# ADX_IDCtoPinheader_adapter_2026-04-28.net
KiCad netlist of a schematic drawn in EasyEDA Pro
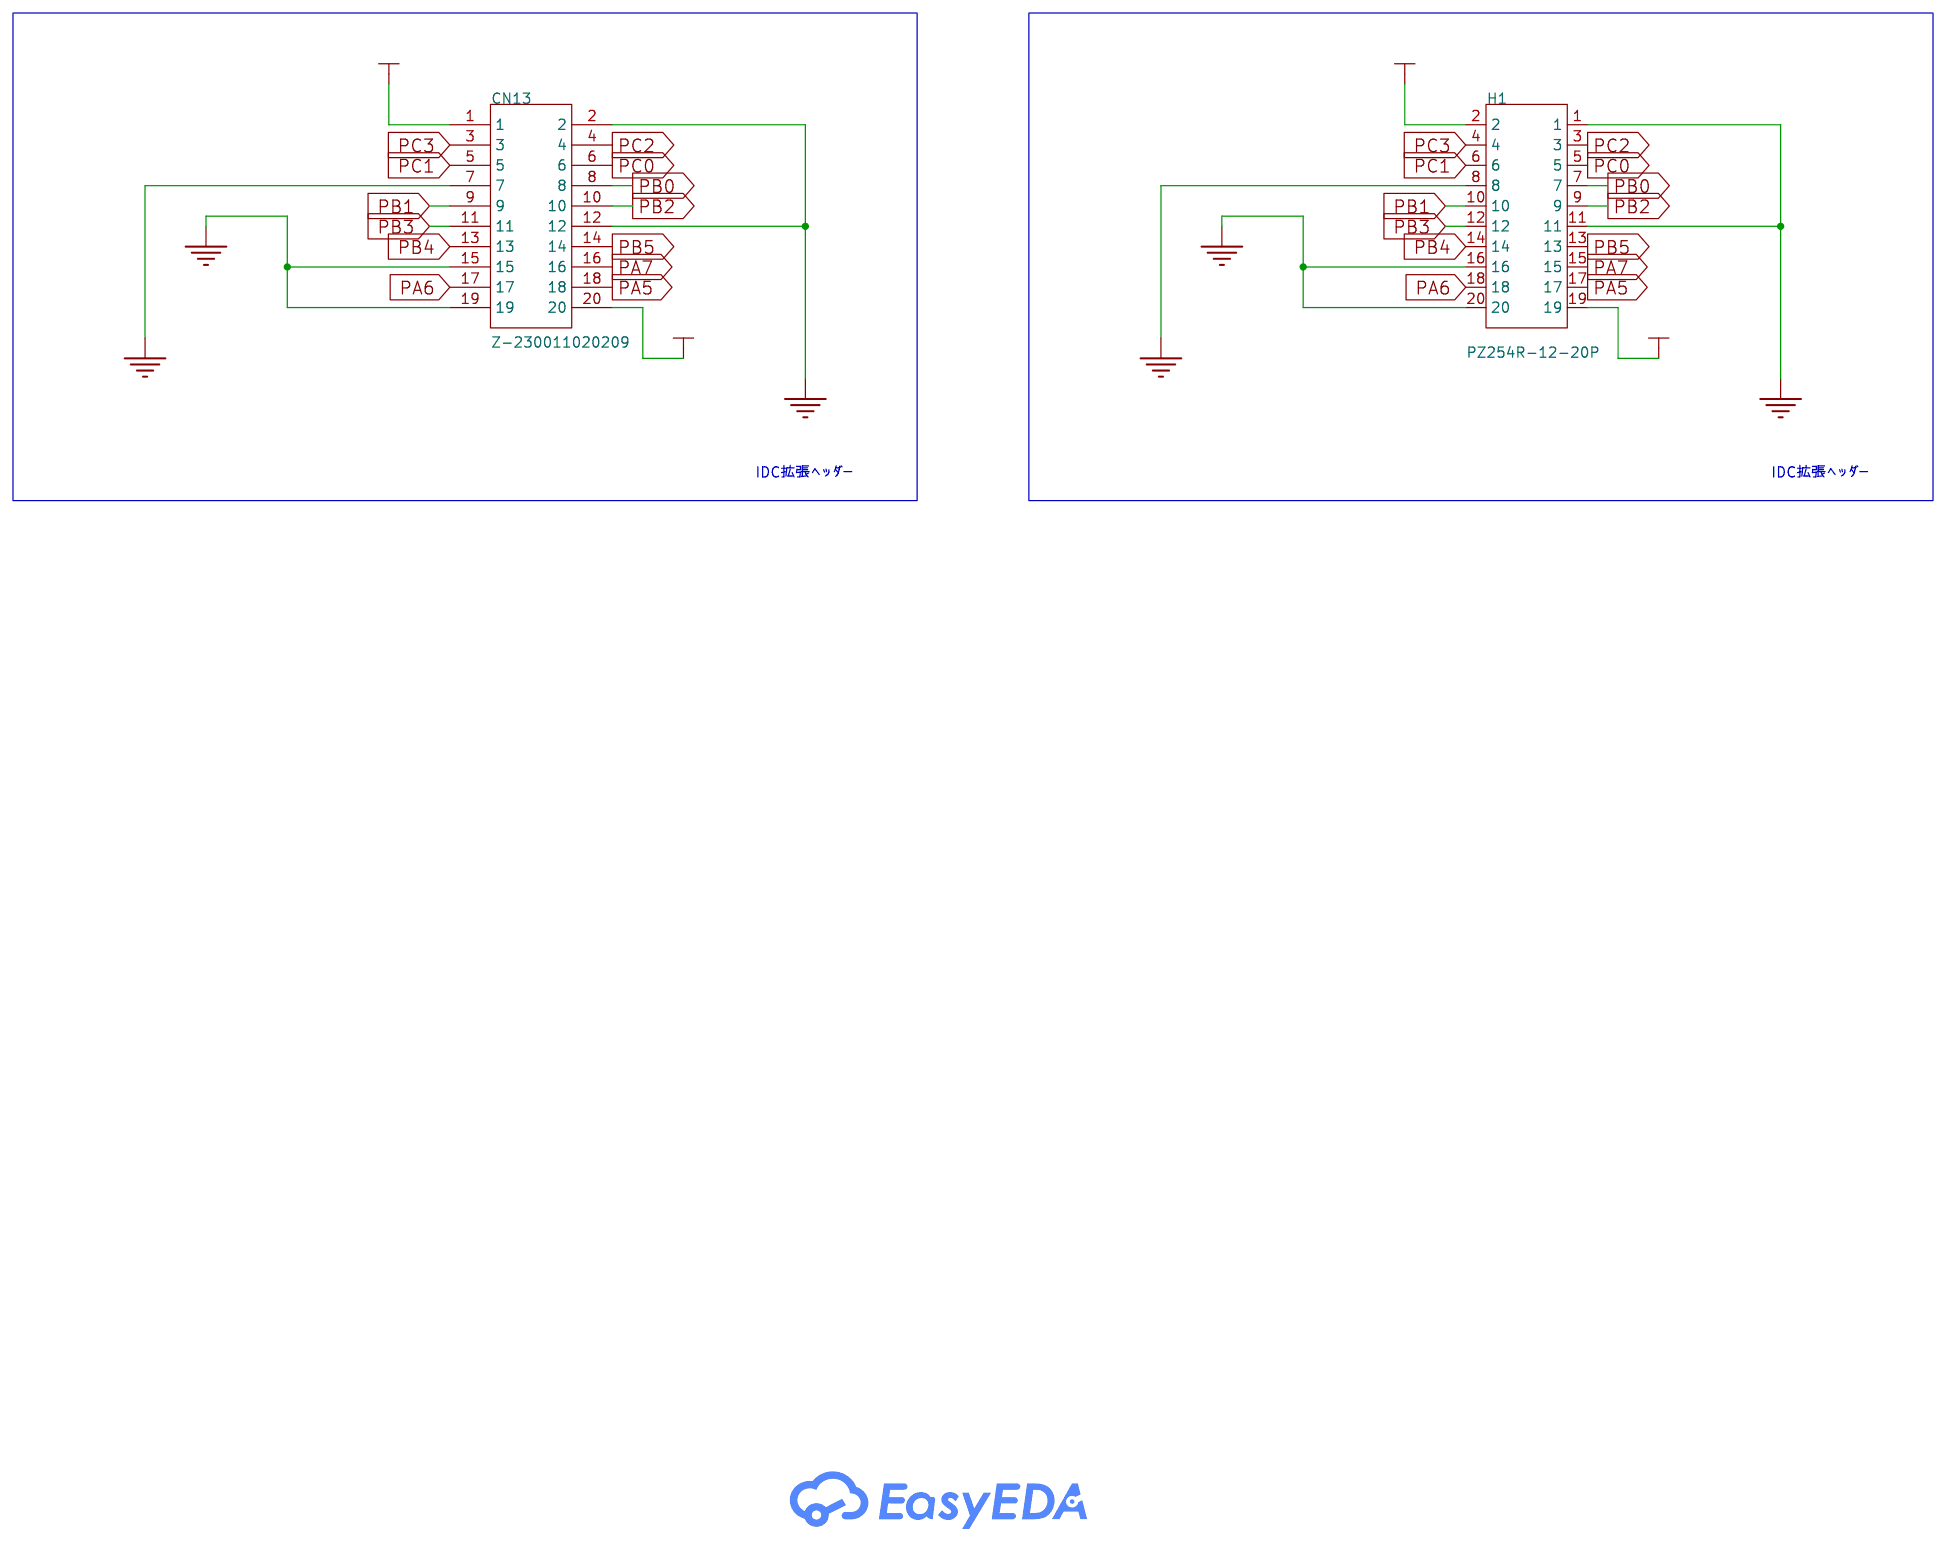
[diagram p0: schematic sheet]

(export (version "E")
  (design (tool "Eeschema 10.0.6"))
  (components
    (comp (ref "CN13")
      (value "Z-230011020209")
      (footprint "easyedapro:IDC-TH_20P-P2.54_Z-230011020209")
      (fields (field (name "Manufacturer") "Nextron(正凌)"))
      (libsource (lib "easyedapro") (part "Z-230011020209"))
    )
    (comp (ref "H1")
      (value "PZ254R-12-20P")
      (footprint "easyedapro:HDR-TH_20P-P2.54-H-M-R2-C10-S2.54")
      (fields (field (name "Manufacturer") "XFCN(兴飞)"))
      (libsource (lib "easyedapro") (part "PZ254R-12-20P"))
    )
  )
  (nets
    (net (code "1") (name "GND_5V") (class "Default")
      (node (ref "CN13") (pin "12") (pinfunction "12_12") (pintype "input"))
      (node (ref "CN13") (pin "15") (pinfunction "15_15") (pintype "input"))
      (node (ref "CN13") (pin "19") (pinfunction "19_19") (pintype "input"))
      (node (ref "CN13") (pin "2") (pinfunction "2_2") (pintype "input"))
      (node (ref "CN13") (pin "7") (pinfunction "7_7") (pintype "input"))
      (node (ref "H1") (pin "1") (pinfunction "1_1") (pintype "unspecified"))
      (node (ref "H1") (pin "11") (pinfunction "11_11") (pintype "unspecified"))
      (node (ref "H1") (pin "16") (pinfunction "16_16") (pintype "unspecified"))
      (node (ref "H1") (pin "20") (pinfunction "20_20") (pintype "unspecified"))
      (node (ref "H1") (pin "8") (pinfunction "8_8") (pintype "unspecified"))
    )
    (net (code "2") (name "PA5") (class "Default")
      (node (ref "CN13") (pin "18") (pinfunction "18_18") (pintype "input"))
      (node (ref "H1") (pin "17") (pinfunction "17_17") (pintype "unspecified"))
    )
    (net (code "3") (name "PA6") (class "Default")
      (node (ref "CN13") (pin "17") (pinfunction "17_17") (pintype "input"))
      (node (ref "H1") (pin "18") (pinfunction "18_18") (pintype "unspecified"))
    )
    (net (code "4") (name "PA7") (class "Default")
      (node (ref "CN13") (pin "16") (pinfunction "16_16") (pintype "input"))
      (node (ref "H1") (pin "15") (pinfunction "15_15") (pintype "unspecified"))
    )
    (net (code "5") (name "PB0") (class "Default")
      (node (ref "CN13") (pin "8") (pinfunction "8_8") (pintype "input"))
      (node (ref "H1") (pin "7") (pinfunction "7_7") (pintype "unspecified"))
    )
    (net (code "6") (name "PB1") (class "Default")
      (node (ref "CN13") (pin "9") (pinfunction "9_9") (pintype "input"))
      (node (ref "H1") (pin "10") (pinfunction "10_10") (pintype "unspecified"))
    )
    (net (code "7") (name "PB2") (class "Default")
      (node (ref "CN13") (pin "10") (pinfunction "10_10") (pintype "input"))
      (node (ref "H1") (pin "9") (pinfunction "9_9") (pintype "unspecified"))
    )
    (net (code "8") (name "PB3") (class "Default")
      (node (ref "CN13") (pin "11") (pinfunction "11_11") (pintype "input"))
      (node (ref "H1") (pin "12") (pinfunction "12_12") (pintype "unspecified"))
    )
    (net (code "9") (name "PB4") (class "Default")
      (node (ref "CN13") (pin "13") (pinfunction "13_13") (pintype "input"))
      (node (ref "H1") (pin "14") (pinfunction "14_14") (pintype "unspecified"))
    )
    (net (code "10") (name "PB5") (class "Default")
      (node (ref "CN13") (pin "14") (pinfunction "14_14") (pintype "input"))
      (node (ref "H1") (pin "13") (pinfunction "13_13") (pintype "unspecified"))
    )
    (net (code "11") (name "PC0") (class "Default")
      (node (ref "CN13") (pin "6") (pinfunction "6_6") (pintype "input"))
      (node (ref "H1") (pin "5") (pinfunction "5_5") (pintype "unspecified"))
    )
    (net (code "12") (name "PC1") (class "Default")
      (node (ref "CN13") (pin "5") (pinfunction "5_5") (pintype "input"))
      (node (ref "H1") (pin "6") (pinfunction "6_6") (pintype "unspecified"))
    )
    (net (code "13") (name "PC2") (class "Default")
      (node (ref "CN13") (pin "4") (pinfunction "4_4") (pintype "input"))
      (node (ref "H1") (pin "3") (pinfunction "3_3") (pintype "unspecified"))
    )
    (net (code "14") (name "PC3") (class "Default")
      (node (ref "CN13") (pin "3") (pinfunction "3_3") (pintype "input"))
      (node (ref "H1") (pin "4") (pinfunction "4_4") (pintype "unspecified"))
    )
    (net (code "15") (name "VDD1") (class "Default")
      (node (ref "CN13") (pin "1") (pinfunction "1_1") (pintype "input"))
      (node (ref "H1") (pin "2") (pinfunction "2_2") (pintype "unspecified"))
    )
    (net (code "16") (name "VDD2") (class "Default")
      (node (ref "CN13") (pin "20") (pinfunction "20_20") (pintype "input"))
      (node (ref "H1") (pin "19") (pinfunction "19_19") (pintype "unspecified"))
    )
  )
)
